# soldering.net
KiCad netlist of a schematic drawn in Altium Designer
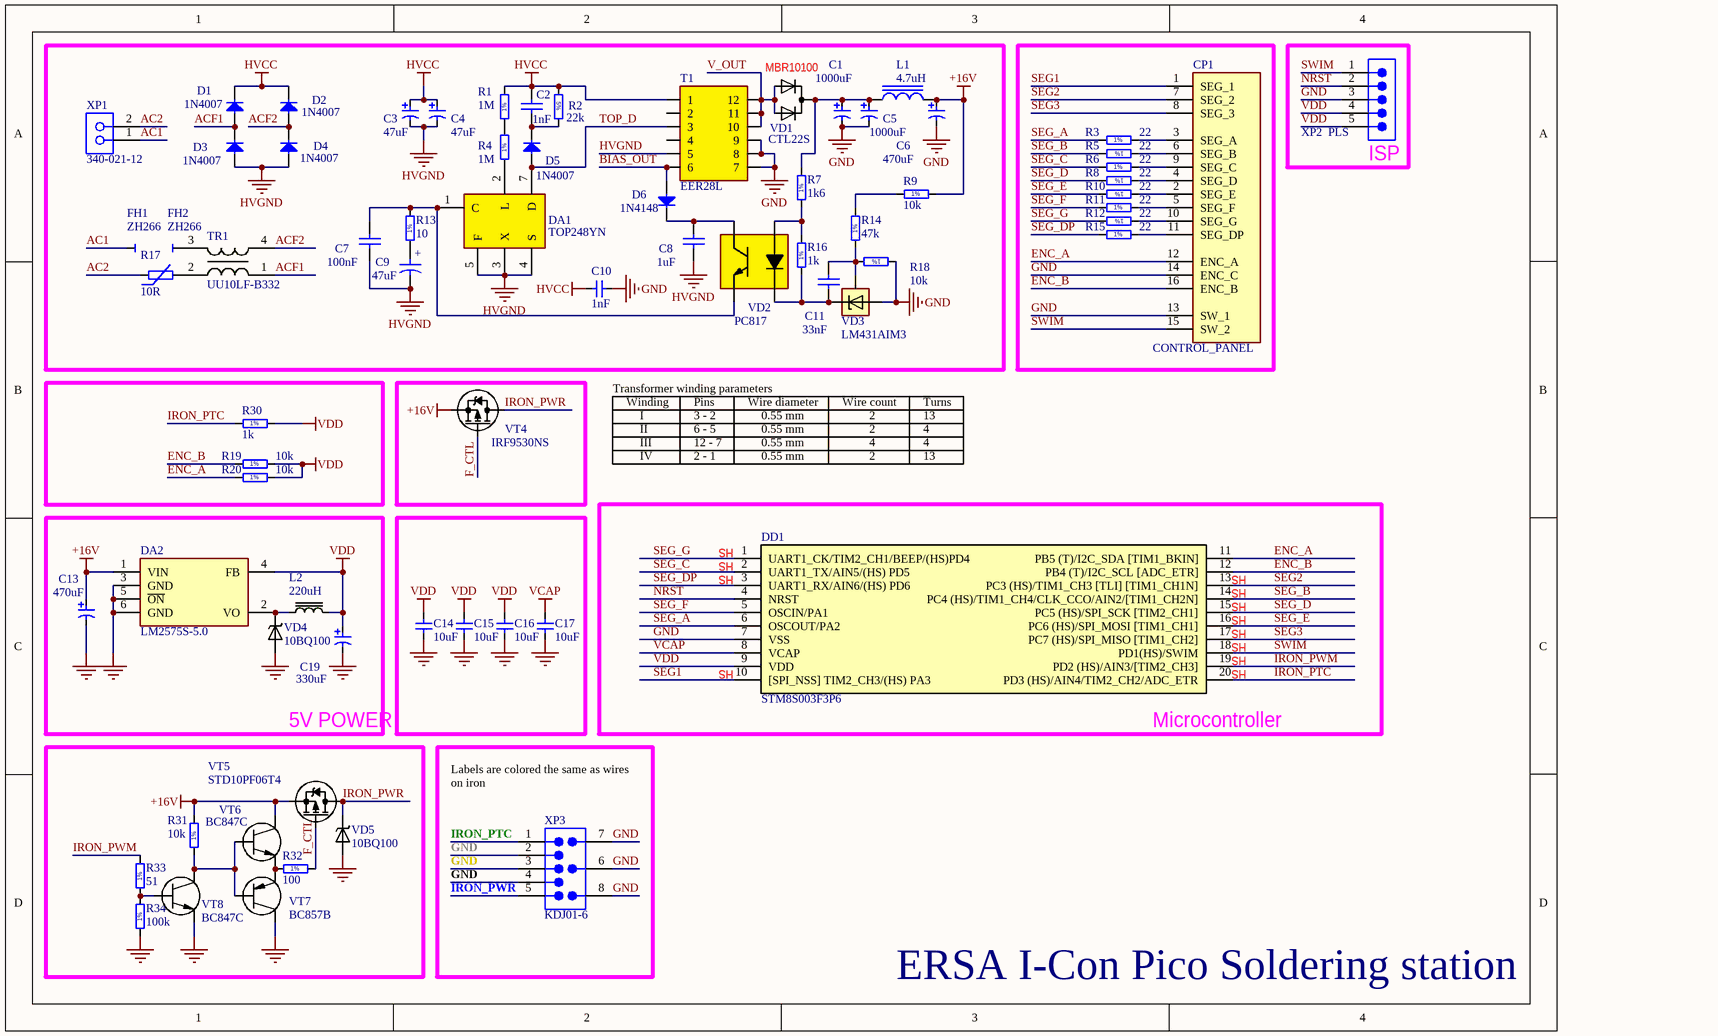
[diagram p0: soldering.SchDoc]

(export (version "E")
  (design (tool "Eeschema 10.0.6"))
  (components
    (comp (ref "C1")
      (value "1000uF")
      (footprint "CAP_EL_13_20_VERT")
      (fields (field (name "PART NUMBER") "SK035M1000B5S-1320 (VERT MOUNTED)") (field (name "VOLTAGE") "35V"))
      (libsource (lib "Capacitor") (part "CAP_POLAR"))
    )
    (comp (ref "C2")
      (value "1nF")
      (footprint "CAPR500-250X720X650")
      (description "Non-polarised capacitor")
      (fields
        (field (name "PART NUMBER") "CPER_1NF_63V_10%_500-250X720X650")
        (field (name "VOLTAGE") "63VDC/40VAC")
        (field (name "AUTHOR") "CERN DEM JLC")
      )
      (libsource (lib "Capacitors") (part "Capacitor - non polarized"))
    )
    (comp (ref "C3")
      (value "47uF")
      (footprint "CAP_EL_16_25_LEFT")
      (fields
        (field (name "PART NUMBER") "SH400M0047B7F-1625 (LEFT MOUNTED)")
        (field (name "VOLTAGE") "400V")
      )
      (libsource (lib "Capacitor") (part "CAP_POLAR"))
    )
    (comp (ref "C4")
      (value "47uF")
      (footprint "CAP_EL_16_25_LEFT")
      (fields
        (field (name "PART NUMBER") "SH400M0047B7F-1625 (LEFT MOUNTED)")
        (field (name "VOLTAGE") "400V")
      )
      (libsource (lib "Capacitor") (part "CAP_POLAR"))
    )
    (comp (ref "C5")
      (value "1000uF")
      (footprint "CAP_EL_13_20_VERT")
      (fields (field (name "PART NUMBER") "SK035M1000B5S-1320 (VERT MOUNTED)") (field (name "VOLTAGE") "35V"))
      (libsource (lib "Capacitor") (part "CAP_POLAR"))
    )
    (comp (ref "C6")
      (value "470uF")
      (footprint "CAP_EL_10_19_VERT")
      (fields (field (name "PART NUMBER") "SJ035M0470B5S-1019 (VERT MOUNTED)") (field (name "VOLTAGE") "35V"))
      (libsource (lib "Capacitor") (part "CAP_POLAR"))
    )
    (comp (ref "C7")
      (value "100nF")
      (footprint "CAPRR508-350X500X500")
      (description "Non-polarised capacitor")
      (fields
        (field (name "PART NUMBER") "CCR_100NF_50V_10%_X7R_508-350X500X500")
        (field (name "VOLTAGE") "50VDC")
        (field (name "AUTHOR") "CERN DEM JLC")
      )
      (libsource (lib "Capacitors") (part "Capacitor - non polarized"))
    )
    (comp (ref "C8")
      (value "1uF")
      (footprint "CAPRR508-508X762X914")
      (description "Non-polarised capacitor")
      (fields
        (field (name "PART NUMBER") "CCR_1UF_50V_10%_X7R_508-508X762X914")
        (field (name "VOLTAGE") "50VDC")
        (field (name "AUTHOR") "CERN DEM JLC")
      )
      (libsource (lib "Capacitors") (part "Capacitor - non polarized"))
    )
    (comp (ref "C9")
      (value "47uF")
      (footprint "CAPPR350-800X1150")
      (description "Polarised capacitor")
      (fields
        (field (name "PART NUMBER") "CAER_47UF_63V_20%_350-800X1150")
        (field (name "VOLTAGE") "63V")
        (field (name "AUTHOR") "CERN DEM JLC")
      )
      (libsource (lib "Capacitors") (part "Capacitor - polarized"))
    )
    (comp (ref "C10")
      (value "1nF")
      (footprint "CAP_7MM_Y")
      (description "SMD 0805 Capacitor")
      (fields (field (name "PART NUMBER") "VKO102KCQTC0KR") (field (name "VOLTAGE") "1000V"))
      (libsource (lib "Capacitor") (part "CAP_NON_POLAR"))
    )
    (comp (ref "C11")
      (value "33nF")
      (footprint "CAPRR254-318X508X660")
      (description "Non-polarised capacitor")
      (fields
        (field (name "PART NUMBER") "CCR_33NF_100V_10%_X7R_254-318X508X660")
        (field (name "VOLTAGE") "100VDC")
        (field (name "AUTHOR") "CERN DEM JLC")
      )
      (libsource (lib "Capacitors") (part "Capacitor - non polarized"))
    )
    (comp (ref "C13")
      (value "470uF")
      (footprint "CAP_EL_10_19_VERT")
      (fields (field (name "PART NUMBER") "SH050M0470B5S-1019 (VERT MOUNTED)") (field (name "VOLTAGE") "50V"))
      (libsource (lib "Capacitor") (part "CAP_POLAR"))
    )
    (comp (ref "C14")
      (value "10uF")
      (footprint "CAP0805R")
      (description "SMD 0805 Capacitor")
      (fields
        (field (name "PART NUMBER") "CC0805_10UF_10V_10%_X7R")
        (field (name "VOLTAGE") "10V")
        (field (name "AUTHOR") "I. Kuznetsov")
      )
      (libsource (lib "Capacitor") (part "CAP_NON_POLAR"))
    )
    (comp (ref "C15")
      (value "10uF")
      (footprint "CAP0805R")
      (description "SMD 0805 Capacitor")
      (fields
        (field (name "PART NUMBER") "CC0805_10UF_10V_10%_X7R")
        (field (name "VOLTAGE") "10V")
        (field (name "AUTHOR") "I. Kuznetsov")
      )
      (libsource (lib "Capacitor") (part "CAP_NON_POLAR"))
    )
    (comp (ref "C16")
      (value "10uF")
      (footprint "CAP0805R")
      (description "SMD 0805 Capacitor")
      (fields
        (field (name "PART NUMBER") "CC0805_10UF_10V_10%_X7R")
        (field (name "VOLTAGE") "10V")
        (field (name "AUTHOR") "I. Kuznetsov")
      )
      (libsource (lib "Capacitor") (part "CAP_NON_POLAR"))
    )
    (comp (ref "C17")
      (value "10uF")
      (footprint "CAP0805R")
      (description "SMD 0805 Capacitor")
      (fields
        (field (name "PART NUMBER") "CC0805_10UF_10V_10%_X7R")
        (field (name "VOLTAGE") "10V")
        (field (name "AUTHOR") "I. Kuznetsov")
      )
      (libsource (lib "Capacitor") (part "CAP_NON_POLAR"))
    )
    (comp (ref "C19")
      (value "330uF")
      (footprint "TAN_D")
      (fields (field (name "PART NUMBER") "T495D337M010AHE100") (field (name "VOLTAGE") "10V"))
      (libsource (lib "Capacitor") (part "CAP_POLAR"))
    )
    (comp (ref "CP1")
      (value "CONTROL_PANEL")
      (footprint "CONTROL_PANEL")
      (libsource (lib "soldering") (part "CONTROL_PANEL"))
    )
    (comp (ref "D1")
      (value "1N4007")
      (footprint "DO-41")
      (description "Diode")
      (fields
        (field (name "VOLTAGE") "1000V")
        (field (name "POWER") "1A")
        (field (name "AUTHOR") "CERN DEM JLC")
      )
      (libsource (lib "ICs And Semiconductors") (part "Diode"))
    )
    (comp (ref "D2")
      (value "1N4007")
      (footprint "DO-41")
      (description "Diode")
      (fields
        (field (name "VOLTAGE") "1000V")
        (field (name "POWER") "1A")
        (field (name "AUTHOR") "CERN DEM JLC")
      )
      (libsource (lib "ICs And Semiconductors") (part "Diode"))
    )
    (comp (ref "D3")
      (value "1N4007")
      (footprint "DO-41")
      (description "Diode")
      (fields
        (field (name "VOLTAGE") "1000V")
        (field (name "POWER") "1A")
        (field (name "AUTHOR") "CERN DEM JLC")
      )
      (libsource (lib "ICs And Semiconductors") (part "Diode"))
    )
    (comp (ref "D4")
      (value "1N4007")
      (footprint "DO-41")
      (description "Diode")
      (fields
        (field (name "VOLTAGE") "1000V")
        (field (name "POWER") "1A")
        (field (name "AUTHOR") "CERN DEM JLC")
      )
      (libsource (lib "ICs And Semiconductors") (part "Diode"))
    )
    (comp (ref "D5")
      (value "1N4007")
      (footprint "DO-41")
      (description "Diode")
      (fields
        (field (name "VOLTAGE") "1000V")
        (field (name "POWER") "1A")
        (field (name "AUTHOR") "CERN DEM JLC")
      )
      (libsource (lib "ICs And Semiconductors") (part "Diode"))
    )
    (comp (ref "D6")
      (value "1N4148")
      (footprint "DO-35")
      (description "Diode")
      (fields
        (field (name "VOLTAGE") "100V")
        (field (name "POWER") "200mA")
        (field (name "AUTHOR") "CERN DEM JLC")
      )
      (libsource (lib "ICs And Semiconductors") (part "Diode"))
    )
    (comp (ref "DA1")
      (value "TOP248YN")
      (footprint "TO-220-7")
      (libsource (lib "IC And Semiconductor") (part "TOP24x"))
    )
    (comp (ref "DA2")
      (value "LM2575S-5.0")
      (footprint "TO-263-5")
      (fields (field (name "MANUFACTURER") "TI") (field (name "AUTHOR") "I. Kuznetsov"))
      (libsource (lib "IC And Semiconductor") (part "LM2575S"))
    )
    (comp (ref "DD1")
      (value "8 Bit MCU")
      (footprint "TSSOP20")
      (description "8 Bit MCU (STmicroelectronics)")
      (fields (field (name "PARTNUMBER") "STM8S003F3P6"))
      (libsource (lib "soldering") (part "STM8S003F3P6"))
    )
    (comp (ref "FH1") (value "ZH266") (footprint "ZH266") (libsource (lib "Connector") (part "Fuse Clip")))
    (comp (ref "FH2") (value "ZH266") (footprint "ZH266") (libsource (lib "Connector") (part "Fuse Clip")))
    (comp (ref "L1")
      (value "4.7uH")
      (footprint "SL1016")
      (fields (field (name "PART NUMBER") "SL1016-4R7K 4.7"))
      (libsource (lib "Transformer") (part "CORE_IND"))
    )
    (comp (ref "L2")
      (value "220uH")
      (footprint "SDR1005")
      (fields (field (name "PART NUMBER") "SDR1005-221KL"))
      (libsource (lib "Transformer") (part "Core_Inductor"))
    )
    (comp (ref "R1")
      (value "1M")
      (footprint "RES_AXIAL_0_25_8")
      (fields
        (field (name "PART NUMBER") "RMF_1M_1%_0.6W_50PPM_1016-630X250")
        (field (name "POWER") "0.6W")
        (field (name "TOLERANCE") "±1%")
        (field (name "AUTHOR") "CERN DEM JLC")
      )
      (libsource (lib "Resistor") (part "Resistor - 1%"))
    )
    (comp (ref "R2")
      (value "22k")
      (footprint "RESADV508-1670X520")
      (description "Resistor - 5%")
      (fields
        (field (name "PART NUMBER") "RMF_22K_5%_3W_250PPM_508-1670X520_v")
        (field (name "POWER") "3W")
        (field (name "AUTHOR") "CERN DEM JLC")
      )
      (libsource (lib "Resistors") (part "Resistor - 5%"))
    )
    (comp (ref "R3")
      (value "22")
      (footprint "RES0805R")
      (fields
        (field (name "PART NUMBER") "R0805_22R_1%_0.125W_100PPM")
        (field (name "POWER") "0.125W")
        (field (name "TOLERANCE") "±1%")
        (field (name "AUTHOR") "CERN DEM JLC")
      )
      (libsource (lib "Resistor") (part "Resistor - 1%"))
    )
    (comp (ref "R4")
      (value "1M")
      (footprint "RES_AXIAL_0_25_8")
      (fields
        (field (name "PART NUMBER") "RMF_1M_1%_0.6W_50PPM_1016-630X250")
        (field (name "POWER") "0.6W")
        (field (name "TOLERANCE") "±1%")
        (field (name "AUTHOR") "CERN DEM JLC")
      )
      (libsource (lib "Resistor") (part "Resistor - 1%"))
    )
    (comp (ref "R5")
      (value "22")
      (footprint "RES0805R")
      (fields
        (field (name "PART NUMBER") "R0805_22R_1%_0.125W_100PPM")
        (field (name "POWER") "0.125W")
        (field (name "TOLERANCE") "±1%")
        (field (name "AUTHOR") "CERN DEM JLC")
      )
      (libsource (lib "Resistor") (part "Resistor - 1%"))
    )
    (comp (ref "R6")
      (value "22")
      (footprint "RES0805R")
      (fields
        (field (name "PART NUMBER") "R0805_22R_1%_0.125W_100PPM")
        (field (name "POWER") "0.125W")
        (field (name "TOLERANCE") "±1%")
        (field (name "AUTHOR") "CERN DEM JLC")
      )
      (libsource (lib "Resistor") (part "Resistor - 1%"))
    )
    (comp (ref "R7")
      (value "1k6")
      (footprint "RES_AXIAL_0_25_8")
      (fields
        (field (name "PART NUMBER") "RMF_1K6_1%_0.6W_50PPM_1016-630X250")
        (field (name "POWER") "0.6W")
        (field (name "TOLERANCE") "±1%")
        (field (name "AUTHOR") "CERN DEM JLC")
      )
      (libsource (lib "Resistor") (part "Resistor - 1%"))
    )
    (comp (ref "R8")
      (value "22")
      (footprint "RES0805R")
      (fields
        (field (name "PART NUMBER") "R0805_22R_1%_0.125W_100PPM")
        (field (name "POWER") "0.125W")
        (field (name "TOLERANCE") "±1%")
        (field (name "AUTHOR") "CERN DEM JLC")
      )
      (libsource (lib "Resistor") (part "Resistor - 1%"))
    )
    (comp (ref "R9")
      (value "10k")
      (footprint "RES_AXIAL_0_25_8")
      (fields
        (field (name "PART NUMBER") "RMF_10K_1%_0.6W_50PPM_1016-630X250")
        (field (name "POWER") "0.6W")
        (field (name "TOLERANCE") "±1%")
        (field (name "AUTHOR") "CERN DEM JLC")
      )
      (libsource (lib "Resistor") (part "Resistor - 1%"))
    )
    (comp (ref "R10")
      (value "22")
      (footprint "RES0805R")
      (fields
        (field (name "PART NUMBER") "R0805_22R_1%_0.125W_100PPM")
        (field (name "POWER") "0.125W")
        (field (name "TOLERANCE") "±1%")
        (field (name "AUTHOR") "CERN DEM JLC")
      )
      (libsource (lib "Resistor") (part "Resistor - 1%"))
    )
    (comp (ref "R11")
      (value "22")
      (footprint "RES0805R")
      (fields
        (field (name "PART NUMBER") "R0805_22R_1%_0.125W_100PPM")
        (field (name "POWER") "0.125W")
        (field (name "TOLERANCE") "±1%")
        (field (name "AUTHOR") "CERN DEM JLC")
      )
      (libsource (lib "Resistor") (part "Resistor - 1%"))
    )
    (comp (ref "R12")
      (value "22")
      (footprint "RES0805R")
      (fields
        (field (name "PART NUMBER") "R0805_22R_1%_0.125W_100PPM")
        (field (name "POWER") "0.125W")
        (field (name "TOLERANCE") "±1%")
        (field (name "AUTHOR") "CERN DEM JLC")
      )
      (libsource (lib "Resistor") (part "Resistor - 1%"))
    )
    (comp (ref "R13")
      (value "10")
      (footprint "RES_AXIAL_0_25_8")
      (fields
        (field (name "PART NUMBER") "RMF_10R_1%_0.6W_50PPM_1016-630X250")
        (field (name "POWER") "0.6W")
        (field (name "TOLERANCE") "±1%")
        (field (name "AUTHOR") "CERN DEM JLC")
      )
      (libsource (lib "Resistor") (part "Resistor - 1%"))
    )
    (comp (ref "R14")
      (value "47k")
      (footprint "RES_AXIAL_0_25_8")
      (fields
        (field (name "PART NUMBER") "RMF_47K_1%_0.6W_50PPM_1016-630X250")
        (field (name "POWER") "0.6W")
        (field (name "TOLERANCE") "±1%")
        (field (name "AUTHOR") "CERN DEM JLC")
      )
      (libsource (lib "Resistor") (part "Resistor - 1%"))
    )
    (comp (ref "R15")
      (value "22")
      (footprint "RES0805R")
      (fields
        (field (name "PART NUMBER") "R0805_22R_1%_0.125W_100PPM")
        (field (name "POWER") "0.125W")
        (field (name "TOLERANCE") "±1%")
        (field (name "AUTHOR") "CERN DEM JLC")
      )
      (libsource (lib "Resistor") (part "Resistor - 1%"))
    )
    (comp (ref "R16")
      (value "1k")
      (footprint "RES_AXIAL_0_25_8")
      (fields
        (field (name "PART NUMBER") "RMF_1K_1%_0.6W_50PPM_1016-630X250")
        (field (name "POWER") "0.6W")
        (field (name "TOLERANCE") "±1%")
        (field (name "AUTHOR") "CERN DEM JLC")
      )
      (libsource (lib "Resistor") (part "Resistor - 1%"))
    )
    (comp (ref "R17")
      (value "10R")
      (footprint "B57164K")
      (fields (field (name "PART NUMBER") "B57164K"))
      (libsource (lib "Resistor") (part "Resistor - Thermo"))
    )
    (comp (ref "R18")
      (value "10k")
      (footprint "RES_AXIAL_0_25_8")
      (fields
        (field (name "PART NUMBER") "RMF_10K_1%_0.6W_50PPM_1016-630X250")
        (field (name "POWER") "0.6W")
        (field (name "TOLERANCE") "±1%")
        (field (name "AUTHOR") "CERN DEM JLC")
      )
      (libsource (lib "Resistor") (part "Resistor - 1%"))
    )
    (comp (ref "R19")
      (value "10k")
      (footprint "RES0805R")
      (fields
        (field (name "PART NUMBER") "R0805_10K_1%_0.125W_100PPM")
        (field (name "POWER") "0.125W")
        (field (name "TOLERANCE") "±1%")
        (field (name "AUTHOR") "CERN DEM JLC")
      )
      (libsource (lib "Resistor") (part "Resistor - 1%"))
    )
    (comp (ref "R20")
      (value "10k")
      (footprint "RES0805R")
      (fields
        (field (name "PART NUMBER") "R0805_10K_1%_0.125W_100PPM")
        (field (name "POWER") "0.125W")
        (field (name "TOLERANCE") "±1%")
        (field (name "AUTHOR") "CERN DEM JLC")
      )
      (libsource (lib "Resistor") (part "Resistor - 1%"))
    )
    (comp (ref "R30")
      (value "1k")
      (footprint "RES0805R")
      (fields
        (field (name "PART NUMBER") "R0805_1K_1%_0.125W_100PPM")
        (field (name "POWER") "0.125W")
        (field (name "TOLERANCE") "±1%")
        (field (name "AUTHOR") "CERN DEM JLC")
      )
      (libsource (lib "Resistor") (part "Resistor - 1%"))
    )
    (comp (ref "R31")
      (value "10k")
      (footprint "RES0805R")
      (fields
        (field (name "PART NUMBER") "R0805_10K_1%_0.125W_100PPM")
        (field (name "POWER") "0.125W")
        (field (name "TOLERANCE") "±1%")
        (field (name "AUTHOR") "CERN DEM JLC")
      )
      (libsource (lib "Resistor") (part "Resistor - 1%"))
    )
    (comp (ref "R32")
      (value "100")
      (footprint "RES0805R")
      (fields
        (field (name "PART NUMBER") "R0805_100R_1%_0.125W_100PPM")
        (field (name "POWER") "0.125W")
        (field (name "TOLERANCE") "±1%")
        (field (name "AUTHOR") "CERN DEM JLC")
      )
      (libsource (lib "Resistor") (part "Resistor - 1%"))
    )
    (comp (ref "R33")
      (value "51")
      (footprint "RES0805R")
      (fields
        (field (name "PART NUMBER") "R0805_51R_1%_0.125W_100PPM")
        (field (name "POWER") "0.125W")
        (field (name "TOLERANCE") "±1%")
        (field (name "AUTHOR") "CERN DEM JLC")
      )
      (libsource (lib "Resistor") (part "Resistor - 1%"))
    )
    (comp (ref "R34")
      (value "100k")
      (footprint "RES0805R")
      (fields
        (field (name "PART NUMBER") "R0805_100K_1%_0.125W_100PPM")
        (field (name "POWER") "0.125W")
        (field (name "TOLERANCE") "±1%")
        (field (name "AUTHOR") "CERN DEM JLC")
      )
      (libsource (lib "Resistor") (part "Resistor - 1%"))
    )
    (comp (ref "T1")
      (value "EER28L")
      (footprint "EER28L")
      (libsource (lib "Transformer") (part "Coil_Former_12pin"))
    )
    (comp (ref "TR1")
      (value "22mH")
      (footprint "CG00008A")
      (fields (field (name "PARTNUMBER") "UU10LF-B332") (field (name "PART NUMBER") "CG00008A"))
      (libsource (lib "Transformer") (part "AC_Filter"))
    )
    (comp (ref "VD1")
      (value "CTL22S")
      (footprint "TO-220-3")
      (libsource (lib "IC And Semiconductor") (part "D_2P_TO220"))
    )
    (comp (ref "VD2") (value "PC817") (footprint "DIP4") (libsource (lib "Optoelectronics") (part "xx817")))
    (comp (ref "VD3")
      (value "LM431AIM3")
      (footprint "TO92")
      (libsource (lib "IC And Semiconductor") (part "Z_3P_TO92"))
    )
    (comp (ref "VD4")
      (value "10BQ100")
      (footprint "DO-214AA")
      (fields (field (name "MANUFACTURER") "IR") (field (name "AUTHOR") "I. Kuznetsov"))
      (libsource (lib "IC And Semiconductor") (part "Diode - Schottky"))
    )
    (comp (ref "VD5")
      (value "10BQ100")
      (footprint "DO-214AA")
      (fields (field (name "MANUFACTURER") "IR") (field (name "AUTHOR") "I. Kuznetsov"))
      (libsource (lib "IC And Semiconductor") (part "Diode - Schottky"))
    )
    (comp (ref "VT4")
      (value "IRF9530NS")
      (footprint "D2PAK")
      (libsource (lib "IC And Semiconductor") (part "P_CH_MOSFET"))
    )
    (comp (ref "VT5")
      (value "STD10PF06T4")
      (footprint "DPAK")
      (fields (field (name "AUTHOR") "I. Kuznetsov"))
      (libsource (lib "IC And Semiconductor") (part "P_CH_MOSFET"))
    )
    (comp (ref "VT6")
      (value "BC847C")
      (footprint "SOT23")
      (fields (field (name "AUTHOR") "I. Kuznetsov"))
      (libsource (lib "IC And Semiconductor") (part "NPN_BIPOLAR_SOT23"))
    )
    (comp (ref "VT7")
      (value "BC857B")
      (footprint "SOT23")
      (fields (field (name "AUTHOR") "I. Kuznetsov"))
      (libsource (lib "IC And Semiconductor") (part "PNP_BIPOLAR"))
    )
    (comp (ref "VT8")
      (value "BC847C")
      (footprint "SOT23")
      (fields (field (name "AUTHOR") "I. Kuznetsov"))
      (libsource (lib "IC And Semiconductor") (part "NPN_BIPOLAR_SOT23"))
    )
    (comp (ref "XP1")
      (value "340-021-12")
      (footprint "340-021-12")
      (libsource (lib "Connector") (part "CN_02S_1W"))
    )
    (comp (ref "XP2")
      (value "PLS")
      (footprint "PLS-05")
      (fields (field (name "PART NUMBER") "PLS-05") (field (name "MANUFACTURER") "AUK"))
      (libsource (lib "Connector") (part "CN_05P_1W"))
    )
    (comp (ref "XP3") (value "KDJ01-6") (footprint "KDJ01-6") (libsource (lib "Connector") (part "KDJ01-6")))
  )
  (nets
    (net (code "1") (name "+16V") (class "Default")
      (node (ref "C13") (pin "2") (pinfunction "2_2") (pintype "passive"))
      (node (ref "C6") (pin "2") (pinfunction "2_2") (pintype "passive"))
      (node (ref "DA2") (pin "1") (pinfunction "VIN_1") (pintype "passive"))
      (node (ref "L1") (pin "2") (pinfunction "2_2") (pintype "passive"))
      (node (ref "R31") (pin "2") (pinfunction "2_2") (pintype "passive"))
      (node (ref "R9") (pin "2") (pinfunction "2_2") (pintype "passive"))
      (node (ref "VT4") (pin "2") (pinfunction "S_2") (pintype "passive"))
      (node (ref "VT5") (pin "2") (pinfunction "S_2") (pintype "passive"))
      (node (ref "VT6") (pin "3") (pinfunction "C_3") (pintype "passive"))
    )
    (net (code "2") (name "/AC1") (class "Default")
      (node (ref "FH1") (pin "1") (pinfunction "1_1") (pintype "passive"))
      (node (ref "XP1") (pin "1") (pinfunction "1_1") (pintype "passive"))
    )
    (net (code "3") (name "/AC2") (class "Default")
      (node (ref "R17") (pin "1") (pinfunction "1_1") (pintype "passive"))
      (node (ref "XP1") (pin "2") (pinfunction "2_2") (pintype "passive"))
    )
    (net (code "4") (name "/ACF1") (class "Default")
      (node (ref "D1") (pin "2") (pinfunction "A_2") (pintype "passive"))
      (node (ref "D3") (pin "1") (pinfunction "C_1") (pintype "passive"))
      (node (ref "TR1") (pin "1") (pinfunction "1_1") (pintype "passive"))
    )
    (net (code "5") (name "/ACF2") (class "Default")
      (node (ref "D2") (pin "2") (pinfunction "A_2") (pintype "passive"))
      (node (ref "D4") (pin "1") (pinfunction "C_1") (pintype "passive"))
      (node (ref "TR1") (pin "4") (pinfunction "4_4") (pintype "passive"))
    )
    (net (code "6") (name "/BIAS_OUT") (class "Default")
      (node (ref "D6") (pin "2") (pinfunction "A_2") (pintype "passive"))
      (node (ref "T1") (pin "6") (pinfunction "6_6") (pintype "passive"))
    )
    (net (code "7") (name "/ENC_A") (class "Default")
      (node (ref "CP1") (pin "12") (pinfunction "ENC_A_12") (pintype "passive"))
      (node (ref "DD1") (pin "11") (pinfunction "PB5_(T)/I2C_SDA_[TIM1_BKIN]_11") (pintype "passive"))
      (node (ref "R20") (pin "1") (pinfunction "1_1") (pintype "passive"))
    )
    (net (code "8") (name "/ENC_B") (class "Default")
      (node (ref "CP1") (pin "16") (pinfunction "ENC_B_16") (pintype "passive"))
      (node (ref "DD1") (pin "12") (pinfunction "PB4_(T)/I2C_SCL_[ADC_ETR]_12") (pintype "passive"))
      (node (ref "R19") (pin "1") (pinfunction "1_1") (pintype "passive"))
    )
    (net (code "9") (name "/F_CTL") (class "Default")
      (node (ref "R32") (pin "2") (pinfunction "2_2") (pintype "passive"))
      (node (ref "VT4") (pin "1") (pinfunction "G_1") (pintype "passive"))
      (node (ref "VT5") (pin "1") (pinfunction "G_1") (pintype "passive"))
    )
    (net (code "10") (name "/IRON_PTC") (class "Default")
      (node (ref "DD1") (pin "20") (pinfunction "PD3_(HS)/AIN4/TIM2_CH2/ADC_ETR_20") (pintype "passive"))
      (node (ref "R30") (pin "1") (pinfunction "1_1") (pintype "passive"))
      (node (ref "XP3") (pin "1") (pinfunction "1_1") (pintype "passive"))
    )
    (net (code "11") (name "/IRON_PWM") (class "Default")
      (node (ref "DD1") (pin "19") (pinfunction "PD2_(HS)/AIN3/[TIM2_CH3]_19") (pintype "passive"))
      (node (ref "R33") (pin "2") (pinfunction "2_2") (pintype "passive"))
    )
    (net (code "12") (name "/IRON_PWR") (class "Default")
      (node (ref "VD5") (pin "K") (pinfunction "K_K") (pintype "passive"))
      (node (ref "VT4") (pin "3") (pinfunction "D_3") (pintype "passive"))
      (node (ref "VT5") (pin "3") (pinfunction "D_3") (pintype "passive"))
      (node (ref "XP3") (pin "5") (pinfunction "5_5") (pintype "passive"))
    )
    (net (code "13") (name "/NRST") (class "Default")
      (node (ref "DD1") (pin "4") (pinfunction "NRST_4") (pintype "passive"))
      (node (ref "XP2") (pin "2") (pinfunction "2_2") (pintype "passive"))
    )
    (net (code "14") (name "/SEG1") (class "Default")
      (node (ref "CP1") (pin "1") (pinfunction "SEG_1_1") (pintype "passive"))
      (node (ref "DD1") (pin "10") (pinfunction "[SPI_NSS]_TIM2_CH3/(HS)_PA3_10") (pintype "passive"))
    )
    (net (code "15") (name "/SEG2") (class "Default")
      (node (ref "CP1") (pin "7") (pinfunction "SEG_2_7") (pintype "passive"))
      (node (ref "DD1") (pin "13") (pinfunction "PC3_(HS)/TIM1_CH3_[TLI]_[TIM1_CH1N]_13") (pintype "passive"))
    )
    (net (code "16") (name "/SEG3") (class "Default")
      (node (ref "CP1") (pin "8") (pinfunction "SEG_3_8") (pintype "passive"))
      (node (ref "DD1") (pin "17") (pinfunction "PC7_(HS)/SPI_MISO_[TIM1_CH2]_17") (pintype "passive"))
    )
    (net (code "17") (name "/SEG_A") (class "Default")
      (node (ref "DD1") (pin "6") (pinfunction "OSCOUT/PA2_6") (pintype "passive"))
      (node (ref "R3") (pin "1") (pinfunction "1_1") (pintype "passive"))
    )
    (net (code "18") (name "/SEG_B") (class "Default")
      (node (ref "DD1") (pin "14") (pinfunction "PC4_(HS)/TIM1_CH4/CLK_CCO/AIN2/[TIM1_CH2N]_14") (pintype "passive"))
      (node (ref "R5") (pin "2") (pinfunction "2_2") (pintype "passive"))
    )
    (net (code "19") (name "/SEG_C") (class "Default")
      (node (ref "DD1") (pin "2") (pinfunction "UART1_TX/AIN5/(HS)_PD5_2") (pintype "passive"))
      (node (ref "R6") (pin "1") (pinfunction "1_1") (pintype "passive"))
    )
    (net (code "20") (name "/SEG_D") (class "Default")
      (node (ref "DD1") (pin "15") (pinfunction "PC5_(HS)/SPI_SCK_[TIM2_CH1]_15") (pintype "passive"))
      (node (ref "R8") (pin "2") (pinfunction "2_2") (pintype "passive"))
    )
    (net (code "21") (name "/SEG_DP") (class "Default")
      (node (ref "DD1") (pin "3") (pinfunction "UART1_RX/AIN6/(HS)_PD6_3") (pintype "passive"))
      (node (ref "R15") (pin "1") (pinfunction "1_1") (pintype "passive"))
    )
    (net (code "22") (name "/SEG_E") (class "Default")
      (node (ref "DD1") (pin "16") (pinfunction "PC6_(HS)/SPI_MOSI_[TIM1_CH1]_16") (pintype "passive"))
      (node (ref "R10") (pin "2") (pinfunction "2_2") (pintype "passive"))
    )
    (net (code "23") (name "/SEG_F") (class "Default")
      (node (ref "DD1") (pin "5") (pinfunction "OSCIN/PA1_5") (pintype "passive"))
      (node (ref "R11") (pin "1") (pinfunction "1_1") (pintype "passive"))
    )
    (net (code "24") (name "/SEG_G") (class "Default")
      (node (ref "DD1") (pin "1") (pinfunction "UART1_CK/TIM2_CH1/BEEP/(HS)PD4_1") (pintype "passive"))
      (node (ref "R12") (pin "2") (pinfunction "2_2") (pintype "passive"))
    )
    (net (code "25") (name "/SWIM") (class "Default")
      (node (ref "CP1") (pin "15") (pinfunction "SW_2_15") (pintype "passive"))
      (node (ref "DD1") (pin "18") (pinfunction "PD1(HS)/SWIM_18") (pintype "passive"))
      (node (ref "XP2") (pin "1") (pinfunction "1_1") (pintype "passive"))
    )
    (net (code "26") (name "/TOP_D") (class "Default")
      (node (ref "D5") (pin "2") (pinfunction "A_2") (pintype "passive"))
      (node (ref "DA1") (pin "7") (pinfunction "D_7") (pintype "passive"))
      (node (ref "T1") (pin "3") (pinfunction "3_3") (pintype "passive"))
    )
    (net (code "27") (name "/V_OUT") (class "Default")
      (node (ref "T1") (pin "10") (pinfunction "10_10") (pintype "passive"))
      (node (ref "T1") (pin "11") (pinfunction "11_11") (pintype "passive"))
      (node (ref "T1") (pin "12") (pinfunction "12_12") (pintype "passive"))
      (node (ref "VD1") (pin "1") (pinfunction "A_1") (pintype "passive"))
      (node (ref "VD1") (pin "3") (pinfunction "A_3") (pintype "passive"))
    )
    (net (code "28") (name "GND") (class "Default")
      (node (ref "C1") (pin "1") (pinfunction "1_1") (pintype "passive"))
      (node (ref "C10") (pin "2") (pinfunction "2_2") (pintype "passive"))
      (node (ref "C13") (pin "1") (pinfunction "1_1") (pintype "passive"))
      (node (ref "C14") (pin "1") (pinfunction "1_1") (pintype "passive"))
      (node (ref "C15") (pin "1") (pinfunction "1_1") (pintype "passive"))
      (node (ref "C16") (pin "1") (pinfunction "1_1") (pintype "passive"))
      (node (ref "C17") (pin "1") (pinfunction "1_1") (pintype "passive"))
      (node (ref "C19") (pin "1") (pinfunction "1_1") (pintype "passive"))
      (node (ref "C5") (pin "1") (pinfunction "1_1") (pintype "passive"))
      (node (ref "C6") (pin "1") (pinfunction "1_1") (pintype "passive"))
      (node (ref "CP1") (pin "13") (pinfunction "SW_1_13") (pintype "passive"))
      (node (ref "CP1") (pin "14") (pinfunction "ENC_C_14") (pintype "passive"))
      (node (ref "DA2") (pin "3") (pinfunction "GND_3") (pintype "passive"))
      (node (ref "DA2") (pin "5") (pinfunction "~{ON}_5") (pintype "passive"))
      (node (ref "DA2") (pin "6") (pinfunction "GND_6") (pintype "passive"))
      (node (ref "DD1") (pin "7") (pinfunction "VSS_7") (pintype "passive"))
      (node (ref "R18") (pin "1") (pinfunction "1_1") (pintype "passive"))
      (node (ref "R34") (pin "1") (pinfunction "1_1") (pintype "passive"))
      (node (ref "T1") (pin "7") (pinfunction "7_7") (pintype "passive"))
      (node (ref "T1") (pin "8") (pinfunction "8_8") (pintype "passive"))
      (node (ref "T1") (pin "9") (pinfunction "9_9") (pintype "passive"))
      (node (ref "VD3") (pin "2") (pinfunction "A_2") (pintype "passive"))
      (node (ref "VD4") (pin "A") (pinfunction "A_A") (pintype "passive"))
      (node (ref "VD5") (pin "A") (pinfunction "A_A") (pintype "passive"))
      (node (ref "VT7") (pin "3") (pinfunction "C_3") (pintype "passive"))
      (node (ref "VT8") (pin "2") (pinfunction "E_2") (pintype "passive"))
      (node (ref "XP2") (pin "3") (pinfunction "3_3") (pintype "passive"))
      (node (ref "XP3") (pin "2") (pinfunction "2_2") (pintype "passive"))
      (node (ref "XP3") (pin "3") (pinfunction "3_3") (pintype "passive"))
      (node (ref "XP3") (pin "4") (pinfunction "4_4") (pintype "passive"))
      (node (ref "XP3") (pin "6") (pinfunction "6_6") (pintype "passive"))
      (node (ref "XP3") (pin "7") (pinfunction "7_7") (pintype "passive"))
      (node (ref "XP3") (pin "8") (pinfunction "8_8") (pintype "passive"))
    )
    (net (code "29") (name "HVCC") (class "Default")
      (node (ref "C10") (pin "1") (pinfunction "1_1") (pintype "passive"))
      (node (ref "C2") (pin "2") (pinfunction "2_2") (pintype "passive"))
      (node (ref "C3") (pin "2") (pinfunction "2_2") (pintype "passive"))
      (node (ref "C4") (pin "2") (pinfunction "2_2") (pintype "passive"))
      (node (ref "D1") (pin "1") (pinfunction "C_1") (pintype "passive"))
      (node (ref "D2") (pin "1") (pinfunction "C_1") (pintype "passive"))
      (node (ref "R1") (pin "2") (pinfunction "2_2") (pintype "passive"))
      (node (ref "R2") (pin "1") (pinfunction "1_1") (pintype "passive"))
      (node (ref "T1") (pin "1") (pinfunction "1_1") (pintype "passive"))
    )
    (net (code "30") (name "HVGND") (class "Default")
      (node (ref "C3") (pin "1") (pinfunction "1_1") (pintype "passive"))
      (node (ref "C4") (pin "1") (pinfunction "1_1") (pintype "passive"))
      (node (ref "C7") (pin "2") (pinfunction "2_2") (pintype "passive"))
      (node (ref "C8") (pin "1") (pinfunction "1_1") (pintype "passive"))
      (node (ref "C9") (pin "2") (pinfunction "2_2") (pintype "passive"))
      (node (ref "D3") (pin "2") (pinfunction "A_2") (pintype "passive"))
      (node (ref "D4") (pin "2") (pinfunction "A_2") (pintype "passive"))
      (node (ref "DA1") (pin "3") (pinfunction "X_3") (pintype "passive"))
      (node (ref "DA1") (pin "4") (pinfunction "S_4") (pintype "passive"))
      (node (ref "DA1") (pin "5") (pinfunction "F_5") (pintype "passive"))
      (node (ref "T1") (pin "5") (pinfunction "5_5") (pintype "passive"))
    )
    (net (code "31") (name "Net-(C9-Pad1)") (class "Default")
      (node (ref "C9") (pin "1") (pinfunction "1_1") (pintype "passive"))
      (node (ref "R13") (pin "1") (pinfunction "1_1") (pintype "passive"))
    )
    (net (code "32") (name "Net-(CP1-SEG_A)") (class "Default")
      (node (ref "CP1") (pin "3") (pinfunction "SEG_A_3") (pintype "passive"))
      (node (ref "R3") (pin "2") (pinfunction "2_2") (pintype "passive"))
    )
    (net (code "33") (name "Net-(CP1-SEG_B)") (class "Default")
      (node (ref "CP1") (pin "6") (pinfunction "SEG_B_6") (pintype "passive"))
      (node (ref "R5") (pin "1") (pinfunction "1_1") (pintype "passive"))
    )
    (net (code "34") (name "Net-(CP1-SEG_C)") (class "Default")
      (node (ref "CP1") (pin "9") (pinfunction "SEG_C_9") (pintype "passive"))
      (node (ref "R6") (pin "2") (pinfunction "2_2") (pintype "passive"))
    )
    (net (code "35") (name "Net-(CP1-SEG_D)") (class "Default")
      (node (ref "CP1") (pin "4") (pinfunction "SEG_D_4") (pintype "passive"))
      (node (ref "R8") (pin "1") (pinfunction "1_1") (pintype "passive"))
    )
    (net (code "36") (name "Net-(CP1-SEG_DP)") (class "Default")
      (node (ref "CP1") (pin "11") (pinfunction "SEG_DP_11") (pintype "passive"))
      (node (ref "R15") (pin "2") (pinfunction "2_2") (pintype "passive"))
    )
    (net (code "37") (name "Net-(CP1-SEG_E)") (class "Default")
      (node (ref "CP1") (pin "2") (pinfunction "SEG_E_2") (pintype "passive"))
      (node (ref "R10") (pin "1") (pinfunction "1_1") (pintype "passive"))
    )
    (net (code "38") (name "Net-(CP1-SEG_F)") (class "Default")
      (node (ref "CP1") (pin "5") (pinfunction "SEG_F_5") (pintype "passive"))
      (node (ref "R11") (pin "2") (pinfunction "2_2") (pintype "passive"))
    )
    (net (code "39") (name "Net-(CP1-SEG_G)") (class "Default")
      (node (ref "CP1") (pin "10") (pinfunction "SEG_G_10") (pintype "passive"))
      (node (ref "R12") (pin "1") (pinfunction "1_1") (pintype "passive"))
    )
    (net (code "40") (name "Net-(D5-C)") (class "Default")
      (node (ref "C2") (pin "1") (pinfunction "1_1") (pintype "passive"))
      (node (ref "D5") (pin "1") (pinfunction "C_1") (pintype "passive"))
      (node (ref "R2") (pin "2") (pinfunction "2_2") (pintype "passive"))
    )
    (net (code "41") (name "Net-(D6-C)") (class "Default")
      (node (ref "C8") (pin "2") (pinfunction "2_2") (pintype "passive"))
      (node (ref "D6") (pin "1") (pinfunction "C_1") (pintype "passive"))
      (node (ref "VD2") (pin "4") (pinfunction "C_4") (pintype "passive"))
    )
    (net (code "42") (name "Net-(DA1-C)") (class "Default")
      (node (ref "C7") (pin "1") (pinfunction "1_1") (pintype "passive"))
      (node (ref "DA1") (pin "1") (pinfunction "C_1") (pintype "passive"))
      (node (ref "R13") (pin "2") (pinfunction "2_2") (pintype "passive"))
      (node (ref "VD2") (pin "3") (pinfunction "E_3") (pintype "passive"))
    )
    (net (code "43") (name "Net-(DA1-L)") (class "Default")
      (node (ref "DA1") (pin "2") (pinfunction "L_2") (pintype "passive"))
      (node (ref "R4") (pin "1") (pinfunction "1_1") (pintype "passive"))
    )
    (net (code "44") (name "Net-(DA2-VO)") (class "Default")
      (node (ref "DA2") (pin "2") (pinfunction "VO_2") (pintype "passive"))
      (node (ref "L2") (pin "1") (pinfunction "1_1") (pintype "passive"))
      (node (ref "VD4") (pin "K") (pinfunction "K_K") (pintype "passive"))
    )
    (net (code "45") (name "Net-(FH2-Pad1)") (class "Default")
      (node (ref "FH2") (pin "1") (pinfunction "1_1") (pintype "passive"))
      (node (ref "TR1") (pin "3") (pinfunction "3_3") (pintype "passive"))
    )
    (net (code "46") (name "Net-(R1-Pad1)") (class "Default")
      (node (ref "R1") (pin "1") (pinfunction "1_1") (pintype "passive"))
      (node (ref "R4") (pin "2") (pinfunction "2_2") (pintype "passive"))
    )
    (net (code "47") (name "Net-(R14-Pad2)") (class "Default")
      (node (ref "R14") (pin "2") (pinfunction "2_2") (pintype "passive"))
      (node (ref "R9") (pin "1") (pinfunction "1_1") (pintype "passive"))
    )
    (net (code "48") (name "Net-(R17-Pad2)") (class "Default")
      (node (ref "R17") (pin "2") (pinfunction "2_2") (pintype "passive"))
      (node (ref "TR1") (pin "2") (pinfunction "2_2") (pintype "passive"))
    )
    (net (code "49") (name "Net-(VD1-K)") (class "Default")
      (node (ref "C1") (pin "2") (pinfunction "2_2") (pintype "passive"))
      (node (ref "C5") (pin "2") (pinfunction "2_2") (pintype "passive"))
      (node (ref "L1") (pin "1") (pinfunction "1_1") (pintype "passive"))
      (node (ref "R7") (pin "2") (pinfunction "2_2") (pintype "passive"))
      (node (ref "VD1") (pin "2") (pinfunction "K_2") (pintype "passive"))
    )
    (net (code "50") (name "Net-(VD2-A)") (class "Default")
      (node (ref "R16") (pin "2") (pinfunction "2_2") (pintype "passive"))
      (node (ref "R7") (pin "1") (pinfunction "1_1") (pintype "passive"))
      (node (ref "VD2") (pin "1") (pinfunction "A_1") (pintype "passive"))
    )
    (net (code "51") (name "Net-(VD2-K)") (class "Default")
      (node (ref "C11") (pin "2") (pinfunction "2_2") (pintype "passive"))
      (node (ref "R16") (pin "1") (pinfunction "1_1") (pintype "passive"))
      (node (ref "VD2") (pin "2") (pinfunction "K_2") (pintype "passive"))
      (node (ref "VD3") (pin "1") (pinfunction "K_1") (pintype "passive"))
    )
    (net (code "52") (name "Net-(VD3-REF)") (class "Default")
      (node (ref "C11") (pin "1") (pinfunction "1_1") (pintype "passive"))
      (node (ref "R14") (pin "1") (pinfunction "1_1") (pintype "passive"))
      (node (ref "R18") (pin "2") (pinfunction "2_2") (pintype "passive"))
      (node (ref "VD3") (pin "3") (pinfunction "REF_3") (pintype "passive"))
    )
    (net (code "53") (name "Net-(VT6-B)") (class "Default")
      (node (ref "R31") (pin "1") (pinfunction "1_1") (pintype "passive"))
      (node (ref "VT6") (pin "1") (pinfunction "B_1") (pintype "passive"))
      (node (ref "VT7") (pin "1") (pinfunction "B_1") (pintype "passive"))
      (node (ref "VT8") (pin "3") (pinfunction "C_3") (pintype "passive"))
    )
    (net (code "54") (name "Net-(VT6-E)") (class "Default")
      (node (ref "R32") (pin "1") (pinfunction "1_1") (pintype "passive"))
      (node (ref "VT6") (pin "2") (pinfunction "E_2") (pintype "passive"))
      (node (ref "VT7") (pin "2") (pinfunction "E_2") (pintype "passive"))
    )
    (net (code "55") (name "Net-(VT8-B)") (class "Default")
      (node (ref "R33") (pin "1") (pinfunction "1_1") (pintype "passive"))
      (node (ref "R34") (pin "2") (pinfunction "2_2") (pintype "passive"))
      (node (ref "VT8") (pin "1") (pinfunction "B_1") (pintype "passive"))
    )
    (net (code "56") (name "VCAP") (class "Default")
      (node (ref "C17") (pin "2") (pinfunction "2_2") (pintype "passive"))
      (node (ref "DD1") (pin "8") (pinfunction "VCAP_8") (pintype "passive"))
    )
    (net (code "57") (name "VDD") (class "Default")
      (node (ref "C14") (pin "2") (pinfunction "2_2") (pintype "passive"))
      (node (ref "C15") (pin "2") (pinfunction "2_2") (pintype "passive"))
      (node (ref "C16") (pin "2") (pinfunction "2_2") (pintype "passive"))
      (node (ref "C19") (pin "2") (pinfunction "2_2") (pintype "passive"))
      (node (ref "DA2") (pin "4") (pinfunction "FB_4") (pintype "passive"))
      (node (ref "DD1") (pin "9") (pinfunction "VDD_9") (pintype "passive"))
      (node (ref "L2") (pin "2") (pinfunction "2_2") (pintype "passive"))
      (node (ref "R19") (pin "2") (pinfunction "2_2") (pintype "passive"))
      (node (ref "R20") (pin "2") (pinfunction "2_2") (pintype "passive"))
      (node (ref "R30") (pin "2") (pinfunction "2_2") (pintype "passive"))
      (node (ref "XP2") (pin "4") (pinfunction "4_4") (pintype "passive"))
      (node (ref "XP2") (pin "5") (pinfunction "5_5") (pintype "passive"))
    )
    (net (code "58") (name "unconnected-(T1-Pad2)") (class "Default")
      (node (ref "T1") (pin "2") (pinfunction "2_2") (pintype "passive"))
    )
    (net (code "59") (name "unconnected-(T1-Pad4)") (class "Default")
      (node (ref "T1") (pin "4") (pinfunction "4_4") (pintype "passive"))
    )
  )
)
